# Microcontroller.net
KiCad netlist of a schematic drawn in Altium Designer
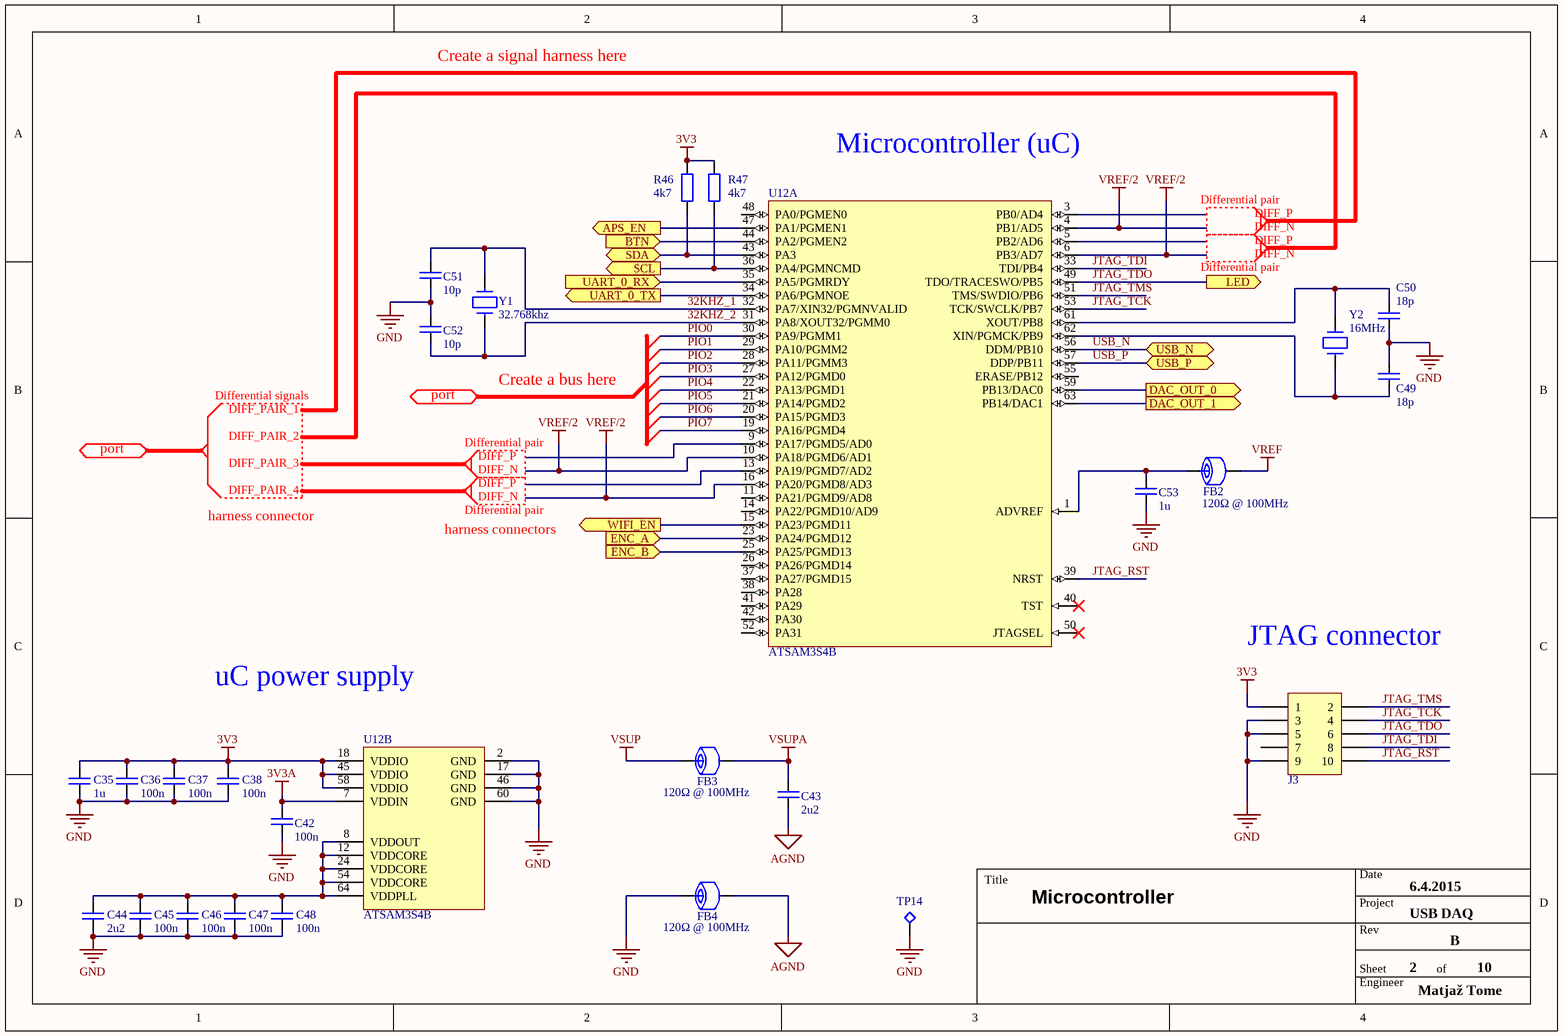
[diagram p0: Microcontroller.SchDoc]

(export (version "E")
  (design (tool "Eeschema 10.0.6"))
  (components
    (comp (ref "C35")
      (value "1u")
      (footprint "C_0603")
      (description "Generic capacitor")
      (libsource (lib "DAQ_REV_B") (part "Capacitor"))
    )
    (comp (ref "C36")
      (value "100n")
      (footprint "C_0603")
      (description "Generic capacitor")
      (libsource (lib "DAQ_REV_B") (part "Capacitor"))
    )
    (comp (ref "C37")
      (value "100n")
      (footprint "C_0603")
      (description "Generic capacitor")
      (libsource (lib "DAQ_REV_B") (part "Capacitor"))
    )
    (comp (ref "C38")
      (value "100n")
      (footprint "C_0603")
      (description "Generic capacitor")
      (libsource (lib "DAQ_REV_B") (part "Capacitor"))
    )
    (comp (ref "C42")
      (value "100n")
      (footprint "C_0603")
      (description "Generic capacitor")
      (libsource (lib "DAQ_REV_B") (part "Capacitor"))
    )
    (comp (ref "C43")
      (value "2u2")
      (footprint "C_0603")
      (description "Generic capacitor")
      (libsource (lib "DAQ_REV_B") (part "Capacitor"))
    )
    (comp (ref "C44")
      (value "2u2")
      (footprint "C_0603")
      (description "Generic capacitor")
      (libsource (lib "DAQ_REV_B") (part "Capacitor"))
    )
    (comp (ref "C45")
      (value "100n")
      (footprint "C_0603")
      (description "Generic capacitor")
      (libsource (lib "DAQ_REV_B") (part "Capacitor"))
    )
    (comp (ref "C46")
      (value "100n")
      (footprint "C_0603")
      (description "Generic capacitor")
      (libsource (lib "DAQ_REV_B") (part "Capacitor"))
    )
    (comp (ref "C47")
      (value "100n")
      (footprint "C_0603")
      (description "Generic capacitor")
      (libsource (lib "DAQ_REV_B") (part "Capacitor"))
    )
    (comp (ref "C48")
      (value "100n")
      (footprint "C_0603")
      (description "Generic capacitor")
      (libsource (lib "DAQ_REV_B") (part "Capacitor"))
    )
    (comp (ref "C49")
      (value "18p")
      (footprint "C_0603")
      (description "Generic capacitor")
      (libsource (lib "DAQ_REV_B") (part "Capacitor"))
    )
    (comp (ref "C50")
      (value "18p")
      (footprint "C_0603")
      (description "Generic capacitor")
      (libsource (lib "DAQ_REV_B") (part "Capacitor"))
    )
    (comp (ref "C51")
      (value "10p")
      (footprint "C_0603")
      (description "Generic capacitor")
      (libsource (lib "DAQ_REV_B") (part "Capacitor"))
    )
    (comp (ref "C52")
      (value "10p")
      (footprint "C_0603")
      (description "Generic capacitor")
      (libsource (lib "DAQ_REV_B") (part "Capacitor"))
    )
    (comp (ref "C53")
      (value "1u")
      (footprint "C_0603")
      (description "Generic capacitor")
      (libsource (lib "DAQ_REV_B") (part "Capacitor"))
    )
    (comp (ref "FB2")
      (value "120Ω @ 100MHz")
      (footprint "SMD_0805")
      (description "Ferrite Bead, 0805 [2012 Metric], 120 ohm, 800 mA, BLM21A Series, 0.15 ohm, ± 25%")
      (fields (field (name "MANUFACTURER") "Murata"))
      (libsource (lib "DAQ_REV_B") (part "BLM21AG121SN1D"))
    )
    (comp (ref "FB3")
      (value "120Ω @ 100MHz")
      (footprint "SMD_0805")
      (description "Ferrite Bead, 0805 [2012 Metric], 120 ohm, 800 mA, BLM21A Series, 0.15 ohm, ± 25%")
      (fields (field (name "MANUFACTURER") "Murata"))
      (libsource (lib "DAQ_REV_B") (part "BLM21AG121SN1D"))
    )
    (comp (ref "FB4")
      (value "120Ω @ 100MHz")
      (footprint "SMD_0805")
      (description "Ferrite Bead, 0805 [2012 Metric], 120 ohm, 800 mA, BLM21A Series, 0.15 ohm, ± 25%")
      (fields (field (name "MANUFACTURER") "Murata"))
      (libsource (lib "DAQ_REV_B") (part "BLM21AG121SN1D"))
    )
    (comp (ref "J3")
      (value "M50-3600542")
      (footprint "HEADER_2X05_1.27mm")
      (description "Pin Header, Board-to-Board, 1.27 mm, 2 Rows, 10 Contacts, Surface Mount, Archer M50 Series")
      (fields (field (name "MANUFACTURER") "Harwin"))
      (libsource (lib "DAQ_REV_B") (part "M50-3600542"))
    )
    (comp (ref "R46")
      (value "4k7")
      (footprint "R_0603")
      (description "Generic resistor")
      (libsource (lib "DAQ_REV_B") (part "Resistor"))
    )
    (comp (ref "R47")
      (value "4k7")
      (footprint "R_0603")
      (description "Generic resistor")
      (libsource (lib "DAQ_REV_B") (part "Resistor"))
    )
    (comp (ref "TP14")
      (value "testpoint")
      (footprint "TP1_FULL")
      (description "testpoint 1.5mm diameter no hole")
      (fields (field (name "PART NUMBER") "XXC0006"))
      (libsource (lib "DAQ_REV_B") (part "Test Point"))
    )
    (comp (ref "U12")
      (value "ATSAM3S4B")
      (footprint "LQFP64")
      (description "Cortex M3 ARM microcontroller")
      (fields (field (name "PART NUMBER") "XAM0003") (field (name "MANUFACTURER") "Atmel"))
      (libsource (lib "DAQ_REV_B") (part "ATSAM3SXB"))
    )
    (comp (ref "Y1")
      (value "32.768khz")
      (footprint "2X6_FLAT")
      (description "Crystal, 32.768 kHz, Cylinder Radial, 6.2mm x 2mm Dia, 12.5 pF, 20 ppm, R26 Series")
      (fields (field (name "PART NUMBER") "XCR0010") (field (name "MANUFACTURER") "RALTRON"))
      (libsource (lib "DAQ_REV_B") (part "R26-32.768- 12.5"))
    )
    (comp (ref "Y2")
      (value "16MHz")
      (footprint "5X3.2")
      (description "Crystal, 16 MHz, SMD, 5mm x 3.2mm, 30 ppm, 18 pF, 30 ppm, 7A Series")
      (fields (field (name "MANUFACTURER") "TCX"))
      (libsource (lib "DAQ_REV_B") (part "7A-16.000MAAJ-T"))
    )
  )
  (nets
    (net (code "1") (name "/32KHZ_1") (class "Default")
      (node (ref "C51") (pin "1") (pinfunction "1_1") (pintype "passive"))
      (node (ref "U12") (pin "32") (pinfunction "PA7/XIN32/PGMNVALID_32") (pintype "bidirectional"))
      (node (ref "Y1") (pin "2") (pinfunction "2_2") (pintype "passive"))
    )
    (net (code "2") (name "/32KHZ_2") (class "Default")
      (node (ref "C52") (pin "1") (pinfunction "1_1") (pintype "passive"))
      (node (ref "U12") (pin "31") (pinfunction "PA8/XOUT32/PGMM0_31") (pintype "bidirectional"))
      (node (ref "Y1") (pin "1") (pinfunction "1_1") (pintype "passive"))
    )
    (net (code "3") (name "/APS_EN") (class "Default")
      (node (ref "U12") (pin "47") (pinfunction "PA1/PGMEN1_47") (pintype "bidirectional"))
    )
    (net (code "4") (name "/BTN") (class "Default")
      (node (ref "U12") (pin "44") (pinfunction "PA2/PGMEN2_44") (pintype "bidirectional"))
    )
    (net (code "5") (name "/DAC_OUT_0") (class "Default")
      (node (ref "U12") (pin "59") (pinfunction "PB13/DAC0_59") (pintype "bidirectional"))
    )
    (net (code "6") (name "/DAC_OUT_1") (class "Default")
      (node (ref "U12") (pin "63") (pinfunction "PB14/DAC1_63") (pintype "bidirectional"))
    )
    (net (code "7") (name "/ENC_A") (class "Default")
      (node (ref "U12") (pin "23") (pinfunction "PA24/PGMD12_23") (pintype "bidirectional"))
    )
    (net (code "8") (name "/ENC_B") (class "Default")
      (node (ref "U12") (pin "25") (pinfunction "PA25/PGMD13_25") (pintype "bidirectional"))
    )
    (net (code "9") (name "/JTAG_RST") (class "Default")
      (node (ref "J3") (pin "10") (pinfunction "10_10") (pintype "passive"))
      (node (ref "U12") (pin "39") (pinfunction "NRST_39") (pintype "bidirectional"))
    )
    (net (code "10") (name "/JTAG_TCK") (class "Default")
      (node (ref "J3") (pin "4") (pinfunction "4_4") (pintype "passive"))
      (node (ref "U12") (pin "53") (pinfunction "TCK/SWCLK/PB7_53") (pintype "bidirectional"))
    )
    (net (code "11") (name "/JTAG_TDI") (class "Default")
      (node (ref "J3") (pin "8") (pinfunction "8_8") (pintype "passive"))
      (node (ref "U12") (pin "33") (pinfunction "TDI/PB4_33") (pintype "bidirectional"))
    )
    (net (code "12") (name "/JTAG_TDO") (class "Default")
      (node (ref "J3") (pin "6") (pinfunction "6_6") (pintype "passive"))
      (node (ref "U12") (pin "49") (pinfunction "TDO/TRACESWO/PB5_49") (pintype "bidirectional"))
    )
    (net (code "13") (name "/JTAG_TMS") (class "Default")
      (node (ref "J3") (pin "2") (pinfunction "2_2") (pintype "passive"))
      (node (ref "U12") (pin "51") (pinfunction "TMS/SWDIO/PB6_51") (pintype "bidirectional"))
    )
    (net (code "14") (name "/PIO0") (class "Default")
      (node (ref "U12") (pin "30") (pinfunction "PA9/PGMM1_30") (pintype "bidirectional"))
    )
    (net (code "15") (name "/PIO1") (class "Default")
      (node (ref "U12") (pin "29") (pinfunction "PA10/PGMM2_29") (pintype "bidirectional"))
    )
    (net (code "16") (name "/PIO2") (class "Default")
      (node (ref "U12") (pin "28") (pinfunction "PA11/PGMM3_28") (pintype "bidirectional"))
    )
    (net (code "17") (name "/PIO3") (class "Default")
      (node (ref "U12") (pin "27") (pinfunction "PA12/PGMD0_27") (pintype "bidirectional"))
    )
    (net (code "18") (name "/PIO4") (class "Default")
      (node (ref "U12") (pin "22") (pinfunction "PA13/PGMD1_22") (pintype "bidirectional"))
    )
    (net (code "19") (name "/PIO5") (class "Default")
      (node (ref "U12") (pin "21") (pinfunction "PA14/PGMD2_21") (pintype "bidirectional"))
    )
    (net (code "20") (name "/PIO6") (class "Default")
      (node (ref "U12") (pin "20") (pinfunction "PA15/PGMD3_20") (pintype "bidirectional"))
    )
    (net (code "21") (name "/PIO7") (class "Default")
      (node (ref "U12") (pin "19") (pinfunction "PA16/PGMD4_19") (pintype "bidirectional"))
    )
    (net (code "22") (name "/SCL") (class "Default")
      (node (ref "R47") (pin "1") (pintype "passive"))
      (node (ref "U12") (pin "36") (pinfunction "PA4/PGMNCMD_36") (pintype "bidirectional"))
    )
    (net (code "23") (name "/SDA") (class "Default")
      (node (ref "R46") (pin "1") (pintype "passive"))
      (node (ref "U12") (pin "43") (pinfunction "PA3_43") (pintype "bidirectional"))
    )
    (net (code "24") (name "/UART_0_RX") (class "Default")
      (node (ref "U12") (pin "35") (pinfunction "PA5/PGMRDY_35") (pintype "bidirectional"))
    )
    (net (code "25") (name "/UART_0_TX") (class "Default")
      (node (ref "U12") (pin "34") (pinfunction "PA6/PGMNOE_34") (pintype "bidirectional"))
    )
    (net (code "26") (name "/USB_N") (class "Default")
      (node (ref "U12") (pin "56") (pinfunction "DDM/PB10_56") (pintype "bidirectional"))
    )
    (net (code "27") (name "/USB_P") (class "Default")
      (node (ref "U12") (pin "57") (pinfunction "DDP/PB11_57") (pintype "bidirectional"))
    )
    (net (code "28") (name "/WIFI_EN") (class "Default")
      (node (ref "U12") (pin "15") (pinfunction "PA23/PGMD11_15") (pintype "bidirectional"))
    )
    (net (code "29") (name "3V3") (class "Default")
      (node (ref "C35") (pin "1") (pinfunction "1_1") (pintype "passive"))
      (node (ref "C36") (pin "1") (pinfunction "1_1") (pintype "passive"))
      (node (ref "C37") (pin "1") (pinfunction "1_1") (pintype "passive"))
      (node (ref "C38") (pin "1") (pinfunction "1_1") (pintype "passive"))
      (node (ref "J3") (pin "1") (pinfunction "1_1") (pintype "passive"))
      (node (ref "R46") (pin "2") (pintype "passive"))
      (node (ref "R47") (pin "2") (pintype "passive"))
      (node (ref "U12") (pin "18") (pinfunction "VDDIO_18") (pintype "power_in"))
      (node (ref "U12") (pin "45") (pinfunction "VDDIO_45") (pintype "power_in"))
      (node (ref "U12") (pin "58") (pinfunction "VDDIO_58") (pintype "power_in"))
    )
    (net (code "30") (name "3V3A") (class "Default")
      (node (ref "C42") (pin "1") (pinfunction "1_1") (pintype "passive"))
      (node (ref "U12") (pin "7") (pinfunction "VDDIN_7") (pintype "power_in"))
    )
    (net (code "31") (name "AGND") (class "Default")
      (node (ref "C43") (pin "2") (pinfunction "2_2") (pintype "passive"))
      (node (ref "FB4") (pin "2") (pintype "passive"))
    )
    (net (code "32") (name "GND") (class "Default")
      (node (ref "C35") (pin "2") (pinfunction "2_2") (pintype "passive"))
      (node (ref "C36") (pin "2") (pinfunction "2_2") (pintype "passive"))
      (node (ref "C37") (pin "2") (pinfunction "2_2") (pintype "passive"))
      (node (ref "C38") (pin "2") (pinfunction "2_2") (pintype "passive"))
      (node (ref "C42") (pin "2") (pinfunction "2_2") (pintype "passive"))
      (node (ref "C44") (pin "2") (pinfunction "2_2") (pintype "passive"))
      (node (ref "C45") (pin "2") (pinfunction "2_2") (pintype "passive"))
      (node (ref "C46") (pin "2") (pinfunction "2_2") (pintype "passive"))
      (node (ref "C47") (pin "2") (pinfunction "2_2") (pintype "passive"))
      (node (ref "C48") (pin "2") (pinfunction "2_2") (pintype "passive"))
      (node (ref "C49") (pin "2") (pinfunction "2_2") (pintype "passive"))
      (node (ref "C50") (pin "2") (pinfunction "2_2") (pintype "passive"))
      (node (ref "C51") (pin "2") (pinfunction "2_2") (pintype "passive"))
      (node (ref "C52") (pin "2") (pinfunction "2_2") (pintype "passive"))
      (node (ref "C53") (pin "2") (pinfunction "2_2") (pintype "passive"))
      (node (ref "FB4") (pin "1") (pintype "passive"))
      (node (ref "J3") (pin "3") (pinfunction "3_3") (pintype "passive"))
      (node (ref "J3") (pin "5") (pinfunction "5_5") (pintype "passive"))
      (node (ref "J3") (pin "9") (pinfunction "9_9") (pintype "passive"))
      (node (ref "TP14") (pin "1") (pinfunction "1_1") (pintype "passive"))
      (node (ref "U12") (pin "17") (pinfunction "GND_17") (pintype "power_in"))
      (node (ref "U12") (pin "2") (pinfunction "GND_2") (pintype "power_in"))
      (node (ref "U12") (pin "46") (pinfunction "GND_46") (pintype "power_in"))
      (node (ref "U12") (pin "60") (pinfunction "GND_60") (pintype "power_in"))
    )
    (net (code "33") (name "Net-(U12A-ADVREF)") (class "Default")
      (node (ref "C53") (pin "1") (pinfunction "1_1") (pintype "passive"))
      (node (ref "FB2") (pin "1") (pintype "passive"))
      (node (ref "U12") (pin "1") (pinfunction "ADVREF_1") (pintype "input"))
    )
    (net (code "34") (name "Net-(U12A-XIN{slash}PGMCK{slash}PB9)") (class "Default")
      (node (ref "C49") (pin "1") (pinfunction "1_1") (pintype "passive"))
      (node (ref "U12") (pin "62") (pinfunction "XIN/PGMCK/PB9_62") (pintype "bidirectional"))
      (node (ref "Y2") (pin "1") (pinfunction "1_1") (pintype "passive"))
    )
    (net (code "35") (name "Net-(U12A-XOUT{slash}PB8)") (class "Default")
      (node (ref "C50") (pin "1") (pinfunction "1_1") (pintype "passive"))
      (node (ref "U12") (pin "61") (pinfunction "XOUT/PB8_61") (pintype "bidirectional"))
      (node (ref "Y2") (pin "2") (pinfunction "2_2") (pintype "passive"))
    )
    (net (code "36") (name "Net-(U12B-VDDOUT)") (class "Default")
      (node (ref "C44") (pin "1") (pinfunction "1_1") (pintype "passive"))
      (node (ref "C45") (pin "1") (pinfunction "1_1") (pintype "passive"))
      (node (ref "C46") (pin "1") (pinfunction "1_1") (pintype "passive"))
      (node (ref "C47") (pin "1") (pinfunction "1_1") (pintype "passive"))
      (node (ref "C48") (pin "1") (pinfunction "1_1") (pintype "passive"))
      (node (ref "U12") (pin "12") (pinfunction "VDDCORE_12") (pintype "power_in"))
      (node (ref "U12") (pin "24") (pinfunction "VDDCORE_24") (pintype "power_in"))
      (node (ref "U12") (pin "54") (pinfunction "VDDCORE_54") (pintype "power_in"))
      (node (ref "U12") (pin "64") (pinfunction "VDDPLL_64") (pintype "power_in"))
      (node (ref "U12") (pin "8") (pinfunction "VDDOUT_8") (pintype "power_in"))
    )
    (net (code "37") (name "VREF") (class "Default") (node (ref "FB2") (pin "2") (pintype "passive")))
    (net (code "38") (name "VREF{slash}2") (class "Default")
      (node (ref "U12") (pin "10") (pinfunction "PA18/PGMD6/AD1_10") (pintype "bidirectional"))
      (node (ref "U12") (pin "16") (pinfunction "PA20/PGMD8/AD3_16") (pintype "bidirectional"))
      (node (ref "U12") (pin "4") (pinfunction "PB1/AD5_4") (pintype "bidirectional"))
      (node (ref "U12") (pin "6") (pinfunction "PB3/AD7_6") (pintype "bidirectional"))
    )
    (net (code "39") (name "VSUP") (class "Default") (node (ref "FB3") (pin "1") (pintype "passive")))
    (net (code "40") (name "VSUPA") (class "Default")
      (node (ref "C43") (pin "1") (pinfunction "1_1") (pintype "passive"))
      (node (ref "FB3") (pin "2") (pintype "passive"))
    )
    (net (code "41") (name "unconnected-(J3-Pad7)") (class "Default")
      (node (ref "J3") (pin "7") (pinfunction "7_7") (pintype "passive"))
    )
    (net (code "42") (name "unconnected-(U12A-ERASE{slash}PB12-Pad55)") (class "Default")
      (node (ref "U12") (pin "55") (pinfunction "ERASE/PB12_55") (pintype "bidirectional"))
    )
    (net (code "43") (name "unconnected-(U12A-JTAGSEL-Pad50)") (class "Default")
      (node (ref "U12") (pin "50") (pinfunction "JTAGSEL_50") (pintype "input+no_connect"))
    )
    (net (code "44") (name "unconnected-(U12A-PA0{slash}PGMEN0-Pad48)") (class "Default")
      (node (ref "U12") (pin "48") (pinfunction "PA0/PGMEN0_48") (pintype "bidirectional"))
    )
    (net (code "45") (name "unconnected-(U12A-PA17{slash}PGMD5{slash}AD0-Pad9)") (class "Default")
      (node (ref "U12") (pin "9") (pinfunction "PA17/PGMD5/AD0_9") (pintype "bidirectional"))
    )
    (net (code "46") (name "unconnected-(U12A-PA19{slash}PGMD7{slash}AD2-Pad13)") (class "Default")
      (node (ref "U12") (pin "13") (pinfunction "PA19/PGMD7/AD2_13") (pintype "bidirectional"))
    )
    (net (code "47") (name "unconnected-(U12A-PA21{slash}PGMD9{slash}AD8-Pad11)") (class "Default")
      (node (ref "U12") (pin "11") (pinfunction "PA21/PGMD9/AD8_11") (pintype "bidirectional"))
    )
    (net (code "48") (name "unconnected-(U12A-PA22{slash}PGMD10{slash}AD9-Pad14)") (class "Default")
      (node (ref "U12") (pin "14") (pinfunction "PA22/PGMD10/AD9_14") (pintype "bidirectional"))
    )
    (net (code "49") (name "unconnected-(U12A-PA26{slash}PGMD14-Pad26)") (class "Default")
      (node (ref "U12") (pin "26") (pinfunction "PA26/PGMD14_26") (pintype "bidirectional"))
    )
    (net (code "50") (name "unconnected-(U12A-PA27{slash}PGMD15-Pad37)") (class "Default")
      (node (ref "U12") (pin "37") (pinfunction "PA27/PGMD15_37") (pintype "bidirectional"))
    )
    (net (code "51") (name "unconnected-(U12A-PA28-Pad38)") (class "Default")
      (node (ref "U12") (pin "38") (pinfunction "PA28_38") (pintype "bidirectional"))
    )
    (net (code "52") (name "unconnected-(U12A-PA29-Pad41)") (class "Default")
      (node (ref "U12") (pin "41") (pinfunction "PA29_41") (pintype "bidirectional"))
    )
    (net (code "53") (name "unconnected-(U12A-PA30-Pad42)") (class "Default")
      (node (ref "U12") (pin "42") (pinfunction "PA30_42") (pintype "bidirectional"))
    )
    (net (code "54") (name "unconnected-(U12A-PA31-Pad52)") (class "Default")
      (node (ref "U12") (pin "52") (pinfunction "PA31_52") (pintype "bidirectional"))
    )
    (net (code "55") (name "unconnected-(U12A-PB0{slash}AD4-Pad3)") (class "Default")
      (node (ref "U12") (pin "3") (pinfunction "PB0/AD4_3") (pintype "bidirectional"))
    )
    (net (code "56") (name "unconnected-(U12A-PB2{slash}AD6-Pad5)") (class "Default")
      (node (ref "U12") (pin "5") (pinfunction "PB2/AD6_5") (pintype "bidirectional"))
    )
    (net (code "57") (name "unconnected-(U12A-TST-Pad40)") (class "Default")
      (node (ref "U12") (pin "40") (pinfunction "TST_40") (pintype "input+no_connect"))
    )
  )
)
